# MS5837_for_Cal_V1_0.net
KiCad netlist of a schematic drawn in Altium Designer
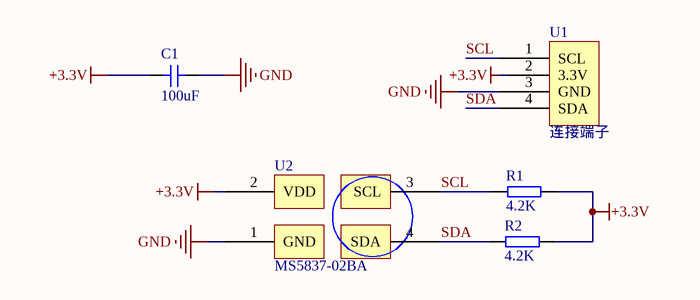
[diagram p0: MS5837 for Cal V1.0.SchDoc]

(export (version "E")
  (design (tool "Eeschema 10.0.6"))
  (components
    (comp (ref "C1")
      (value "100uF")
      (footprint "0603C")
      (description "无极贴片电容")
      (libsource (lib "集大电协1.5(1)") (part "Cap1"))
    )
    (comp (ref "R1")
      (value "4.2K")
      (footprint "0603R")
      (description "电阻")
      (libsource (lib "集大电协1.1.5") (part "Res"))
    )
    (comp (ref "R2")
      (value "4.2K")
      (footprint "0603R")
      (description "电阻")
      (libsource (lib "集大电协1.1.5") (part "Res"))
    )
    (comp (ref "U1") (value "连接端子") (footprint "连接端子") (libsource (lib "集大电协1.1.5") (part "连接端子")))
    (comp (ref "U2")
      (value "MS5837-02BA")
      (footprint "MS5837-02BA")
      (libsource (lib "集大电协1.5(1)") (part "MS5837-02BA"))
    )
  )
  (nets
    (net (code "1") (name "+3.3V") (class "Default")
      (node (ref "C1") (pin "1") (pinfunction "1_1") (pintype "passive"))
      (node (ref "R1") (pin "2") (pinfunction "2_2") (pintype "passive"))
      (node (ref "R2") (pin "2") (pinfunction "2_2") (pintype "passive"))
      (node (ref "U1") (pin "2") (pinfunction "3.3V_2") (pintype "passive"))
      (node (ref "U2") (pin "2") (pinfunction "VDD_2") (pintype "passive"))
    )
    (net (code "2") (name "/SCL") (class "Default")
      (node (ref "R1") (pin "1") (pinfunction "1_1") (pintype "passive"))
      (node (ref "U1") (pin "1") (pinfunction "SCL_1") (pintype "passive"))
      (node (ref "U2") (pin "3") (pinfunction "SCL_3") (pintype "passive"))
    )
    (net (code "3") (name "/SDA") (class "Default")
      (node (ref "R2") (pin "1") (pinfunction "1_1") (pintype "passive"))
      (node (ref "U1") (pin "4") (pinfunction "SDA_4") (pintype "passive"))
      (node (ref "U2") (pin "4") (pinfunction "SDA_4") (pintype "passive"))
    )
    (net (code "4") (name "GND") (class "Default")
      (node (ref "C1") (pin "2") (pinfunction "2_2") (pintype "passive"))
      (node (ref "U1") (pin "3") (pinfunction "GND_3") (pintype "passive"))
      (node (ref "U2") (pin "1") (pinfunction "GND_1") (pintype "passive"))
    )
  )
)
